# PA_Channel.net
KiCad netlist of a schematic drawn in Altium Designer
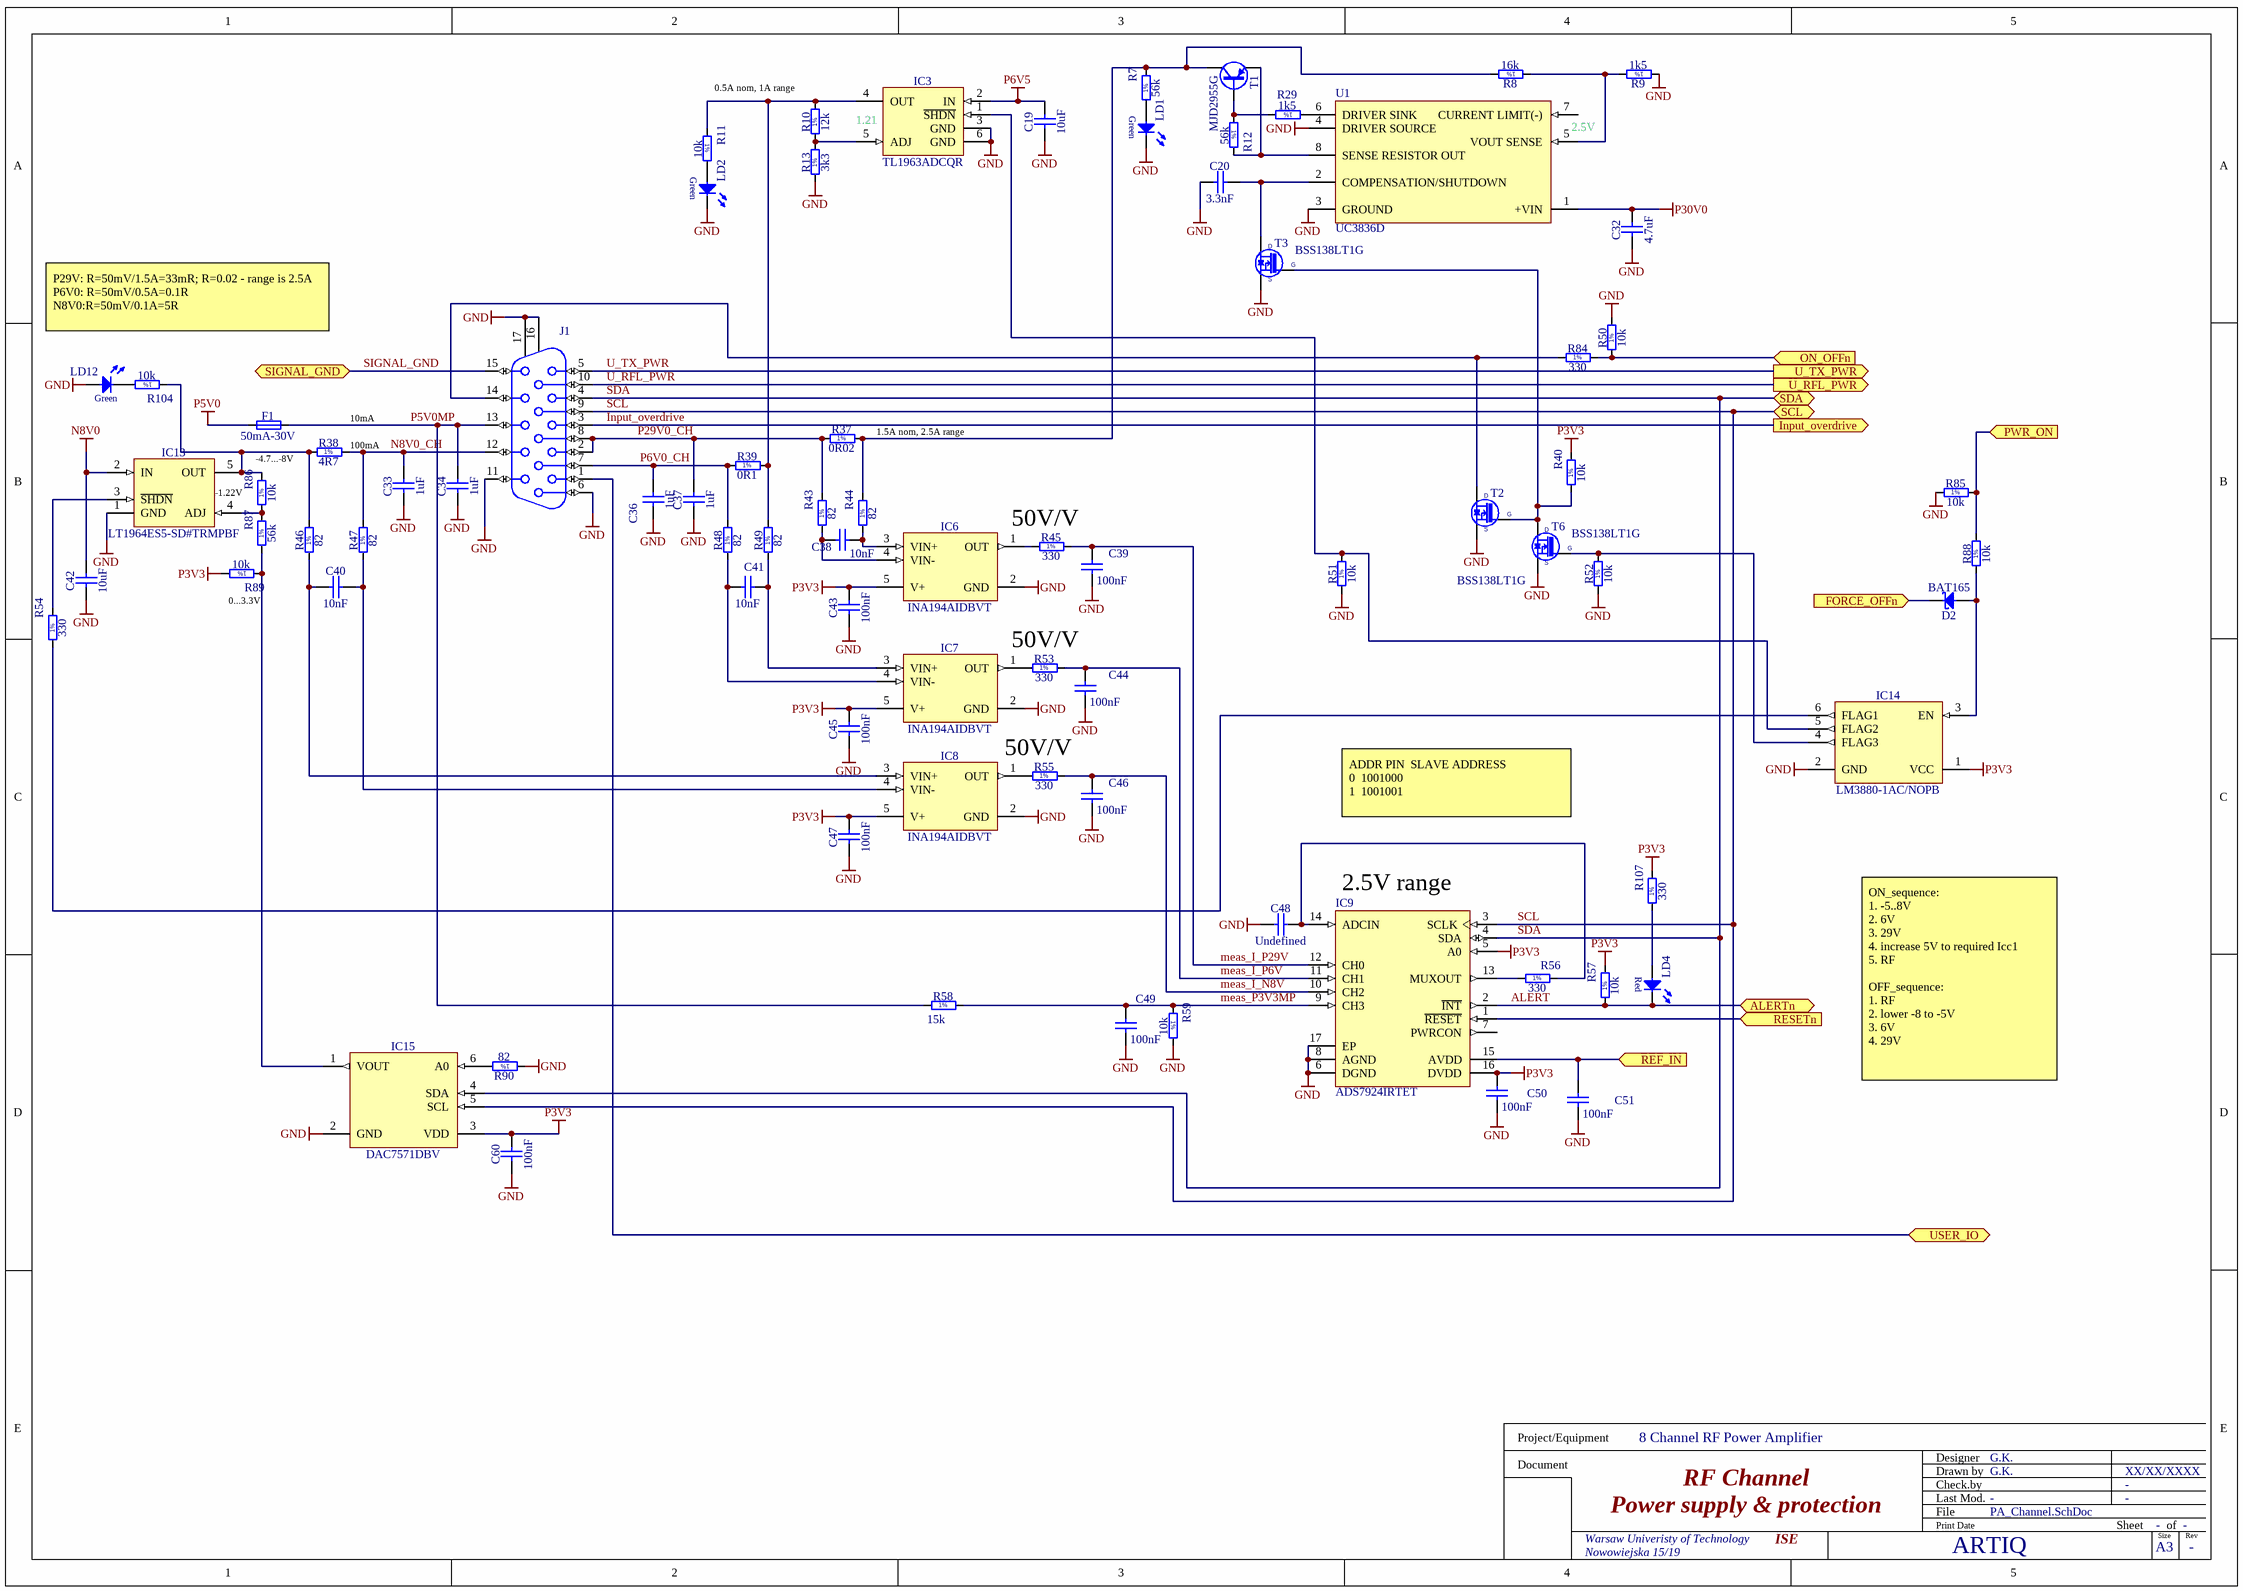
[diagram p0: PA_Channel.SchDoc]

(export (version "E")
  (design (tool "Eeschema 10.0.6"))
  (components
    (comp (ref "C19")
      (value "10uF")
      (footprint "CAPC3216X140N")
      (description "Non-polarised capacitor")
      (fields
        (field (name "PART NUMBER") "CC1206_10UF_16V_10%_X7R")
        (field (name "VOLTAGE") "16V")
        (field (name "AUTHOR") "CERN DEM JLC")
      )
      (libsource (lib "Capacitors") (part "Capacitor - non polarized"))
    )
    (comp (ref "C20")
      (value "3.3nF")
      (footprint "CAPC1005X55N")
      (description "Non-polarised capacitor")
      (fields
        (field (name "PART NUMBER") "CC0402_3.3NF_50V_10%_X7R")
        (field (name "VOLTAGE") "50V")
        (field (name "AUTHOR") "CERN DEM JLC")
      )
      (libsource (lib "Capacitors") (part "Capacitor - non polarized"))
    )
    (comp (ref "C32")
      (value "4.7uF")
      (footprint "CAPC3216X180N")
      (description "Non-polarised capacitor")
      (fields
        (field (name "PART NUMBER") "CC1206_4.7UF_50V_+80%-20%_Y5V")
        (field (name "VOLTAGE") "50V")
        (field (name "AUTHOR") "CERN DEM JLC")
      )
      (libsource (lib "Capacitors") (part "Capacitor - non polarized"))
    )
    (comp (ref "C33")
      (value "1uF")
      (footprint "CAPC2012X110N")
      (description "Non-polarised capacitor")
      (fields
        (field (name "PART NUMBER") "CC0805_1UF_50V_10%_X7R")
        (field (name "VOLTAGE") "50V")
        (field (name "AUTHOR") "CERN DEM JLC")
      )
      (libsource (lib "Capacitors") (part "Capacitor - non polarized"))
    )
    (comp (ref "C34")
      (value "1uF")
      (footprint "CAPC2012X110N")
      (description "Non-polarised capacitor")
      (fields
        (field (name "PART NUMBER") "CC0805_1UF_50V_10%_X7R")
        (field (name "VOLTAGE") "50V")
        (field (name "AUTHOR") "CERN DEM JLC")
      )
      (libsource (lib "Capacitors") (part "Capacitor - non polarized"))
    )
    (comp (ref "C36")
      (value "1uF")
      (footprint "CAPC2012X110N")
      (description "Non-polarised capacitor")
      (fields
        (field (name "PART NUMBER") "CC0805_1UF_50V_10%_X7R")
        (field (name "VOLTAGE") "50V")
        (field (name "AUTHOR") "CERN DEM JLC")
      )
      (libsource (lib "Capacitors") (part "Capacitor - non polarized"))
    )
    (comp (ref "C37")
      (value "1uF")
      (footprint "CAPC2012X110N")
      (description "Non-polarised capacitor")
      (fields
        (field (name "PART NUMBER") "CC0805_1UF_50V_10%_X7R")
        (field (name "VOLTAGE") "50V")
        (field (name "AUTHOR") "CERN DEM JLC")
      )
      (libsource (lib "Capacitors") (part "Capacitor - non polarized"))
    )
    (comp (ref "C38")
      (value "10nF")
      (footprint "CAPC1608X87N")
      (description "Non-polarised capacitor")
      (fields
        (field (name "PART NUMBER") "CC0603_10NF_50V_5%_C0G")
        (field (name "VOLTAGE") "50V")
        (field (name "AUTHOR") "CERN DEM JLC")
      )
      (libsource (lib "Capacitors") (part "Capacitor - non polarized"))
    )
    (comp (ref "C39")
      (value "100nF")
      (footprint "CAPC1005X55N")
      (description "Non-polarised capacitor")
      (fields
        (field (name "PART NUMBER") "CC0402_100NF_16V_10%_X7R")
        (field (name "VOLTAGE") "16V")
        (field (name "AUTHOR") "CERN DEM JLC")
      )
      (libsource (lib "Capacitors") (part "Capacitor - non polarized"))
    )
    (comp (ref "C40")
      (value "10nF")
      (footprint "CAPC1608X87N")
      (description "Non-polarised capacitor")
      (fields
        (field (name "PART NUMBER") "CC0603_10NF_50V_5%_C0G")
        (field (name "VOLTAGE") "50V")
        (field (name "AUTHOR") "CERN DEM JLC")
      )
      (libsource (lib "Capacitors") (part "Capacitor - non polarized"))
    )
    (comp (ref "C41")
      (value "10nF")
      (footprint "CAPC1608X87N")
      (description "Non-polarised capacitor")
      (fields
        (field (name "PART NUMBER") "CC0603_10NF_50V_5%_C0G")
        (field (name "VOLTAGE") "50V")
        (field (name "AUTHOR") "CERN DEM JLC")
      )
      (libsource (lib "Capacitors") (part "Capacitor - non polarized"))
    )
    (comp (ref "C42")
      (value "10uF")
      (footprint "CAPC3216X140N")
      (description "Non-polarised capacitor")
      (fields
        (field (name "PART NUMBER") "CC1206_10UF_16V_10%_X7R")
        (field (name "VOLTAGE") "16V")
        (field (name "AUTHOR") "CERN DEM JLC")
      )
      (libsource (lib "Capacitors") (part "Capacitor - non polarized"))
    )
    (comp (ref "C43")
      (value "100nF")
      (footprint "CAPC1005X55N")
      (description "Non-polarised capacitor")
      (fields
        (field (name "PART NUMBER") "CC0402_100NF_16V_10%_X7R")
        (field (name "VOLTAGE") "16V")
        (field (name "AUTHOR") "CERN DEM JLC")
      )
      (libsource (lib "Capacitors") (part "Capacitor - non polarized"))
    )
    (comp (ref "C44")
      (value "100nF")
      (footprint "CAPC1005X55N")
      (description "Non-polarised capacitor")
      (fields
        (field (name "PART NUMBER") "CC0402_100NF_16V_10%_X7R")
        (field (name "VOLTAGE") "16V")
        (field (name "AUTHOR") "CERN DEM JLC")
      )
      (libsource (lib "Capacitors") (part "Capacitor - non polarized"))
    )
    (comp (ref "C45")
      (value "100nF")
      (footprint "CAPC1005X55N")
      (description "Non-polarised capacitor")
      (fields
        (field (name "PART NUMBER") "CC0402_100NF_16V_10%_X7R")
        (field (name "VOLTAGE") "16V")
        (field (name "AUTHOR") "CERN DEM JLC")
      )
      (libsource (lib "Capacitors") (part "Capacitor - non polarized"))
    )
    (comp (ref "C46")
      (value "100nF")
      (footprint "CAPC1005X55N")
      (description "Non-polarised capacitor")
      (fields
        (field (name "PART NUMBER") "CC0402_100NF_16V_10%_X7R")
        (field (name "VOLTAGE") "16V")
        (field (name "AUTHOR") "CERN DEM JLC")
      )
      (libsource (lib "Capacitors") (part "Capacitor - non polarized"))
    )
    (comp (ref "C47")
      (value "100nF")
      (footprint "CAPC1005X55N")
      (description "Non-polarised capacitor")
      (fields
        (field (name "PART NUMBER") "CC0402_100NF_16V_10%_X7R")
        (field (name "VOLTAGE") "16V")
        (field (name "AUTHOR") "CERN DEM JLC")
      )
      (libsource (lib "Capacitors") (part "Capacitor - non polarized"))
    )
    (comp (ref "C48")
      (value "Undefined")
      (footprint "CAPC1005X55N")
      (description "Non-polarised capacitor")
      (fields (field (name "PART NUMBER") "CC0402_NO-VALUE") (field (name "AUTHOR") "CERN DEM JLC"))
      (libsource (lib "Capacitors") (part "Capacitor - non polarized"))
    )
    (comp (ref "C49")
      (value "100nF")
      (footprint "CAPC1005X55N")
      (description "Non-polarised capacitor")
      (fields
        (field (name "PART NUMBER") "CC0402_100NF_16V_10%_X7R")
        (field (name "VOLTAGE") "16V")
        (field (name "AUTHOR") "CERN DEM JLC")
      )
      (libsource (lib "Capacitors") (part "Capacitor - non polarized"))
    )
    (comp (ref "C50")
      (value "100nF")
      (footprint "CAPC1005X55N")
      (description "Non-polarised capacitor")
      (fields
        (field (name "PART NUMBER") "CC0402_100NF_16V_10%_X7R")
        (field (name "VOLTAGE") "16V")
        (field (name "AUTHOR") "CERN DEM JLC")
      )
      (libsource (lib "Capacitors") (part "Capacitor - non polarized"))
    )
    (comp (ref "C51")
      (value "100nF")
      (footprint "CAPC1005X55N")
      (description "Non-polarised capacitor")
      (fields
        (field (name "PART NUMBER") "CC0402_100NF_16V_10%_X7R")
        (field (name "VOLTAGE") "16V")
        (field (name "AUTHOR") "CERN DEM JLC")
      )
      (libsource (lib "Capacitors") (part "Capacitor - non polarized"))
    )
    (comp (ref "C60")
      (value "100nF")
      (footprint "CAPC1005X55N")
      (description "Non-polarised capacitor")
      (fields
        (field (name "PART NUMBER") "CC0402_100NF_16V_10%_X7R")
        (field (name "VOLTAGE") "16V")
        (field (name "AUTHOR") "CERN DEM JLC")
      )
      (libsource (lib "Capacitors") (part "Capacitor - non polarized"))
    )
    (comp (ref "D2")
      (value "BAT165")
      (footprint "SOD2512X110N")
      (description "Schottky Diode")
      (fields
        (field (name "VOLTAGE") "40V")
        (field (name "POWER") "750mA")
        (field (name "AUTHOR") "CERN DEM JLC")
      )
      (libsource (lib "ICs And Semiconductors") (part "Diode Schottky"))
    )
    (comp (ref "F1")
      (value "50mA-30V")
      (footprint "FUSRC3226X85N")
      (description "Fuse")
      (fields
        (field (name "PART NUMBER") "FUSR1210_TYCO-MICROSMD005F")
        (field (name "MANUFACTURER") "TYCO ELECTRONICS")
        (field (name "AUTHOR") "CERN DEM JLC")
      )
      (libsource (lib "Eletro-mechanical") (part "Fuse"))
    )
    (comp (ref "IC3")
      (value "TL1963ADCQR")
      (footprint "SOT127P700X180-6N")
      (description "1.2V to 20V, 1.5A, Fast Transient Response, Low Noise, LDO Adjustable Regulator")
      (fields (field (name "MANUFACTURER") "TEXAS INSTRUMENTS") (field (name "AUTHOR") "CERN DEM JLC"))
      (libsource (lib "ICs And Semiconductors") (part "TL1963ADCQR"))
    )
    (comp (ref "IC6")
      (value "INA194AIDBVT")
      (footprint "SOT95P280X145-5N")
      (description "Current Shunt Monitor -16V to +80V Common-Mode Range")
      (fields (field (name "MANUFACTURER") "TEXAS INSTRUMENTS") (field (name "AUTHOR") "CERN DEM JLC"))
      (libsource (lib "ICs And Semiconductors") (part "INA194"))
    )
    (comp (ref "IC7")
      (value "INA194AIDBVT")
      (footprint "SOT95P280X145-5N")
      (description "Current Shunt Monitor -16V to +80V Common-Mode Range")
      (fields (field (name "MANUFACTURER") "TEXAS INSTRUMENTS") (field (name "AUTHOR") "CERN DEM JLC"))
      (libsource (lib "ICs And Semiconductors") (part "INA194"))
    )
    (comp (ref "IC8")
      (value "INA194AIDBVT")
      (footprint "SOT95P280X145-5N")
      (description "Current Shunt Monitor -16V to +80V Common-Mode Range")
      (fields (field (name "MANUFACTURER") "TEXAS INSTRUMENTS") (field (name "AUTHOR") "CERN DEM JLC"))
      (libsource (lib "ICs And Semiconductors") (part "INA194"))
    )
    (comp (ref "IC9")
      (value "ADS7924IRTET")
      (footprint "TI-RTE16-1700X1700TP_V")
      (fields (field (name "MANUFACTURER") "Texas Instruments"))
      (libsource (lib "Altium Content Vault") (part "CMP-0003-02162-1"))
    )
    (comp (ref "IC13")
      (value "LT1964ES5-SD#TRMPBF")
      (footprint "SOT95P280X100-5N")
      (description "200mA, Low Noise, Low Dropout Negative Micropower Regulator")
      (fields (field (name "MANUFACTURER") "LINEAR TECHNOLOGY") (field (name "AUTHOR") "CERN DEM JLC"))
      (libsource (lib "ICs And Semiconductors") (part "LT1964-SD"))
    )
    (comp (ref "IC14")
      (value "LM3880-1AC/NOPB")
      (footprint "SOT95P280X145-6N")
      (description "Simple Power Sequencer")
      (fields (field (name "MANUFACTURER") "TEXAS INSTRUMENTS") (field (name "AUTHOR") "CERN DEM MR"))
      (libsource (lib "ICs And Semiconductors") (part "LM3880"))
    )
    (comp (ref "IC15")
      (value "DAC7571DBV")
      (footprint "SOT95P280X145-6N")
      (description "+2.7 V to +5.5 V, I2C Interface (Receive Only), Voltage Output, 12-Bit Digital-To-Analog Converter")
      (fields (field (name "MANUFACTURER") "TEXAS INSTRUMENTS") (field (name "AUTHOR") "CERN DEM MR"))
      (libsource (lib "ICs And Semiconductors") (part "DAC7571"))
    )
    (comp (ref "J1")
      (value "HD-Sub")
      (footprint "TYCO_1932144-1")
      (description "Connector High Density D-sub 15 Female")
      (fields
        (field (name "PART NUMBER") "TYCO_1932144-1")
        (field (name "MANUFACTURER") "TYCO ELECTRONICS")
        (field (name "AUTHOR") "GK")
      )
      (libsource (lib "LIBRARY_SCH") (part "CON_DB15_V_F_1932144-1"))
    )
    (comp (ref "LD1")
      (value "Green")
      (footprint "LED_KINGBRIGHT_KPH-1608CGCK")
      (description "LED Green 1C 2A")
      (fields
        (field (name "PART NUMBER") "LED_KINGBRIGHT_KPH-1608CGCK")
        (field (name "MANUFACTURER") "KINGBRIGHT")
        (field (name "AUTHOR") "CERN DEM JLC")
      )
      (libsource (lib "ICs And Semiconductors") (part "LED Green 1C 2A"))
    )
    (comp (ref "LD2")
      (value "Green")
      (footprint "LED_KINGBRIGHT_KPH-1608CGCK")
      (description "LED Green 1C 2A")
      (fields
        (field (name "PART NUMBER") "LED_KINGBRIGHT_KPH-1608CGCK")
        (field (name "MANUFACTURER") "KINGBRIGHT")
        (field (name "AUTHOR") "CERN DEM JLC")
      )
      (libsource (lib "ICs And Semiconductors") (part "LED Green 1C 2A"))
    )
    (comp (ref "LD4")
      (value "Hyper Red")
      (footprint "LED_KINGBRIGHT_KPH-1608SURCK")
      (description "LED Red 1C 2A")
      (fields
        (field (name "PART NUMBER") "LED_KINGBRIGHT_KPH-1608SURCK")
        (field (name "MANUFACTURER") "KINGBRIGHT")
        (field (name "AUTHOR") "CERN DEM JLC")
      )
      (libsource (lib "ICs And Semiconductors") (part "LED Red 1C 2A"))
    )
    (comp (ref "LD12")
      (value "Green")
      (footprint "LED_KINGBRIGHT_KPH-1608CGCK")
      (description "LED Green 1C 2A")
      (fields
        (field (name "PART NUMBER") "LED_KINGBRIGHT_KPH-1608CGCK")
        (field (name "MANUFACTURER") "KINGBRIGHT")
        (field (name "AUTHOR") "CERN DEM JLC")
      )
      (libsource (lib "ICs And Semiconductors") (part "LED Green 1C 2A"))
    )
    (comp (ref "R7")
      (value "56k")
      (footprint "RESC1608X55N")
      (description "Resistor - 1%")
      (fields
        (field (name "PART NUMBER") "R0603_56K_1%_0.1W_100PPM")
        (field (name "POWER") "0.1W")
        (field (name "AUTHOR") "CERN DEM JLC")
      )
      (libsource (lib "Resistors") (part "Resistor - 1%"))
    )
    (comp (ref "R8")
      (value "16k")
      (footprint "RESC1608X55N")
      (description "Resistor - 1%")
      (fields
        (field (name "PART NUMBER") "R0603_16K_1%_0.1W_100PPM")
        (field (name "POWER") "0.1W")
        (field (name "AUTHOR") "CERN DEM JLC")
      )
      (libsource (lib "Resistors") (part "Resistor - 1%"))
    )
    (comp (ref "R9")
      (value "1k5")
      (footprint "RESC1608X55N")
      (description "Resistor - 1%")
      (fields
        (field (name "PART NUMBER") "R0603_1K5_1%_0.1W_100PPM")
        (field (name "POWER") "0.1W")
        (field (name "AUTHOR") "CERN DEM JLC")
      )
      (libsource (lib "Resistors") (part "Resistor - 1%"))
    )
    (comp (ref "R10")
      (value "12k")
      (footprint "RESC1005X40N")
      (description "Resistor - 1%")
      (fields
        (field (name "PART NUMBER") "R0402_12K_1%_0.0625W_100PPM")
        (field (name "POWER") "0.0625W")
        (field (name "AUTHOR") "CERN DEM JLC")
      )
      (libsource (lib "Resistors") (part "Resistor - 1%"))
    )
    (comp (ref "R11")
      (value "10k")
      (footprint "RESC1005X40N")
      (description "Resistor - 1%")
      (fields
        (field (name "PART NUMBER") "R0402_10K_1%_0.0625W_100PPM")
        (field (name "POWER") "0.0625W")
        (field (name "AUTHOR") "CERN DEM JLC")
      )
      (libsource (lib "Resistors") (part "Resistor - 1%"))
    )
    (comp (ref "R12")
      (value "56k")
      (footprint "RESC1608X55N")
      (description "Resistor - 1%")
      (fields
        (field (name "PART NUMBER") "R0603_56K_1%_0.1W_100PPM")
        (field (name "POWER") "0.1W")
        (field (name "AUTHOR") "CERN DEM JLC")
      )
      (libsource (lib "Resistors") (part "Resistor - 1%"))
    )
    (comp (ref "R13")
      (value "3k3")
      (footprint "RESC1005X40N")
      (description "Resistor - 1%")
      (fields
        (field (name "PART NUMBER") "R0402_3K3_1%_0.0625W_100PPM")
        (field (name "POWER") "0.0625W")
        (field (name "AUTHOR") "CERN DEM JLC")
      )
      (libsource (lib "Resistors") (part "Resistor - 1%"))
    )
    (comp (ref "R29")
      (value "1k5")
      (footprint "RESC1608X55N")
      (description "Resistor - 1%")
      (fields
        (field (name "PART NUMBER") "R0603_1K5_1%_0.1W_100PPM")
        (field (name "POWER") "0.1W")
        (field (name "AUTHOR") "CERN DEM JLC")
      )
      (libsource (lib "Resistors") (part "Resistor - 1%"))
    )
    (comp (ref "R37")
      (value "0R02")
      (footprint "RESC3216X80N")
      (description "Resistor - 1%")
      (fields
        (field (name "PART NUMBER") "R1206_0R02_1%_1W_150PPM")
        (field (name "POWER") "1W")
        (field (name "AUTHOR") "CERN DEM JLC")
      )
      (libsource (lib "Resistors") (part "Resistor - 1%"))
    )
    (comp (ref "R38")
      (value "4R7")
      (footprint "RESC3216X65N")
      (description "Resistor - 1%")
      (fields
        (field (name "PART NUMBER") "R1206_4R7_1%_0.25W_200PPM")
        (field (name "POWER") "0.25W")
        (field (name "AUTHOR") "CERN DEM JLC")
      )
      (libsource (lib "Resistors") (part "Resistor - 1%"))
    )
    (comp (ref "R39")
      (value "0R1")
      (footprint "RESC3216X65N")
      (description "Resistor - 1%")
      (fields
        (field (name "PART NUMBER") "R1206_0R1_1%_0.25W_100PPM_YAGEO_PT")
        (field (name "POWER") "0.25W")
        (field (name "AUTHOR") "CERN DEM JMW")
      )
      (libsource (lib "Resistors") (part "Resistor - 1%"))
    )
    (comp (ref "R40")
      (value "10k")
      (footprint "RESC1005X40N")
      (description "Resistor - 1%")
      (fields
        (field (name "PART NUMBER") "R0402_10K_1%_0.0625W_100PPM")
        (field (name "POWER") "0.0625W")
        (field (name "AUTHOR") "CERN DEM JLC")
      )
      (libsource (lib "Resistors") (part "Resistor - 1%"))
    )
    (comp (ref "R43")
      (value "82")
      (footprint "RESC1005X40N")
      (description "Resistor - 1%")
      (fields
        (field (name "PART NUMBER") "R0402_82R_1%_0.0625W_100PPM")
        (field (name "POWER") "0.0625W")
        (field (name "AUTHOR") "CERN DEM JLC")
      )
      (libsource (lib "Resistors") (part "Resistor - 1%"))
    )
    (comp (ref "R44")
      (value "82")
      (footprint "RESC1005X40N")
      (description "Resistor - 1%")
      (fields
        (field (name "PART NUMBER") "R0402_82R_1%_0.0625W_100PPM")
        (field (name "POWER") "0.0625W")
        (field (name "AUTHOR") "CERN DEM JLC")
      )
      (libsource (lib "Resistors") (part "Resistor - 1%"))
    )
    (comp (ref "R45")
      (value "330")
      (footprint "RESC1608X55N")
      (description "Resistor - 1%")
      (fields
        (field (name "PART NUMBER") "R0603_330R_1%_0.1W_100PPM")
        (field (name "POWER") "0.1W")
        (field (name "AUTHOR") "CERN DEM JLC")
      )
      (libsource (lib "Resistors") (part "Resistor - 1%"))
    )
    (comp (ref "R46")
      (value "82")
      (footprint "RESC1005X40N")
      (description "Resistor - 1%")
      (fields
        (field (name "PART NUMBER") "R0402_82R_1%_0.0625W_100PPM")
        (field (name "POWER") "0.0625W")
        (field (name "AUTHOR") "CERN DEM JLC")
      )
      (libsource (lib "Resistors") (part "Resistor - 1%"))
    )
    (comp (ref "R47")
      (value "82")
      (footprint "RESC1005X40N")
      (description "Resistor - 1%")
      (fields
        (field (name "PART NUMBER") "R0402_82R_1%_0.0625W_100PPM")
        (field (name "POWER") "0.0625W")
        (field (name "AUTHOR") "CERN DEM JLC")
      )
      (libsource (lib "Resistors") (part "Resistor - 1%"))
    )
    (comp (ref "R48")
      (value "82")
      (footprint "RESC1005X40N")
      (description "Resistor - 1%")
      (fields
        (field (name "PART NUMBER") "R0402_82R_1%_0.0625W_100PPM")
        (field (name "POWER") "0.0625W")
        (field (name "AUTHOR") "CERN DEM JLC")
      )
      (libsource (lib "Resistors") (part "Resistor - 1%"))
    )
    (comp (ref "R49")
      (value "82")
      (footprint "RESC1005X40N")
      (description "Resistor - 1%")
      (fields
        (field (name "PART NUMBER") "R0402_82R_1%_0.0625W_100PPM")
        (field (name "POWER") "0.0625W")
        (field (name "AUTHOR") "CERN DEM JLC")
      )
      (libsource (lib "Resistors") (part "Resistor - 1%"))
    )
    (comp (ref "R50")
      (value "10k")
      (footprint "RESC1005X40N")
      (description "Resistor - 1%")
      (fields
        (field (name "PART NUMBER") "R0402_10K_1%_0.0625W_100PPM")
        (field (name "POWER") "0.0625W")
        (field (name "AUTHOR") "CERN DEM JLC")
      )
      (libsource (lib "Resistors") (part "Resistor - 1%"))
    )
    (comp (ref "R51")
      (value "10k")
      (footprint "RESC1005X40N")
      (description "Resistor - 1%")
      (fields
        (field (name "PART NUMBER") "R0402_10K_1%_0.0625W_100PPM")
        (field (name "POWER") "0.0625W")
        (field (name "AUTHOR") "CERN DEM JLC")
      )
      (libsource (lib "Resistors") (part "Resistor - 1%"))
    )
    (comp (ref "R52")
      (value "10k")
      (footprint "RESC1005X40N")
      (description "Resistor - 1%")
      (fields
        (field (name "PART NUMBER") "R0402_10K_1%_0.0625W_100PPM")
        (field (name "POWER") "0.0625W")
        (field (name "AUTHOR") "CERN DEM JLC")
      )
      (libsource (lib "Resistors") (part "Resistor - 1%"))
    )
    (comp (ref "R53")
      (value "330")
      (footprint "RESC1608X55N")
      (description "Resistor - 1%")
      (fields
        (field (name "PART NUMBER") "R0603_330R_1%_0.1W_100PPM")
        (field (name "POWER") "0.1W")
        (field (name "AUTHOR") "CERN DEM JLC")
      )
      (libsource (lib "Resistors") (part "Resistor - 1%"))
    )
    (comp (ref "R54")
      (value "330")
      (footprint "RESC1608X55N")
      (description "Resistor - 1%")
      (fields
        (field (name "PART NUMBER") "R0603_330R_1%_0.1W_100PPM")
        (field (name "POWER") "0.1W")
        (field (name "AUTHOR") "CERN DEM JLC")
      )
      (libsource (lib "Resistors") (part "Resistor - 1%"))
    )
    (comp (ref "R55")
      (value "330")
      (footprint "RESC1608X55N")
      (description "Resistor - 1%")
      (fields
        (field (name "PART NUMBER") "R0603_330R_1%_0.1W_100PPM")
        (field (name "POWER") "0.1W")
        (field (name "AUTHOR") "CERN DEM JLC")
      )
      (libsource (lib "Resistors") (part "Resistor - 1%"))
    )
    (comp (ref "R56")
      (value "330")
      (footprint "RESC1608X55N")
      (description "Resistor - 1%")
      (fields
        (field (name "PART NUMBER") "R0603_330R_1%_0.1W_100PPM")
        (field (name "POWER") "0.1W")
        (field (name "AUTHOR") "CERN DEM JLC")
      )
      (libsource (lib "Resistors") (part "Resistor - 1%"))
    )
    (comp (ref "R57")
      (value "10k")
      (footprint "RESC1005X40N")
      (description "Resistor - 1%")
      (fields
        (field (name "PART NUMBER") "R0402_10K_1%_0.0625W_100PPM")
        (field (name "POWER") "0.0625W")
        (field (name "AUTHOR") "CERN DEM JLC")
      )
      (libsource (lib "Resistors") (part "Resistor - 1%"))
    )
    (comp (ref "R58")
      (value "15k")
      (footprint "RESC1005X40N")
      (description "Resistor - 1%")
      (fields
        (field (name "PART NUMBER") "R0402_15K_1%_0.0625W_100PPM")
        (field (name "POWER") "0.0625W")
        (field (name "AUTHOR") "CERN DEM JMW")
      )
      (libsource (lib "Resistors") (part "Resistor - 1%"))
    )
    (comp (ref "R59")
      (value "10k")
      (footprint "RESC1005X40N")
      (description "Resistor - 1%")
      (fields
        (field (name "PART NUMBER") "R0402_10K_1%_0.0625W_100PPM")
        (field (name "POWER") "0.0625W")
        (field (name "AUTHOR") "CERN DEM JLC")
      )
      (libsource (lib "Resistors") (part "Resistor - 1%"))
    )
    (comp (ref "R84")
      (value "330")
      (footprint "RESC1608X55N")
      (description "Resistor - 1%")
      (fields
        (field (name "PART NUMBER") "R0603_330R_1%_0.1W_100PPM")
        (field (name "POWER") "0.1W")
        (field (name "AUTHOR") "CERN DEM JLC")
      )
      (libsource (lib "Resistors") (part "Resistor - 1%"))
    )
    (comp (ref "R85")
      (value "10k")
      (footprint "RESC1005X40N")
      (description "Resistor - 1%")
      (fields
        (field (name "PART NUMBER") "R0402_10K_1%_0.0625W_100PPM")
        (field (name "POWER") "0.0625W")
        (field (name "AUTHOR") "CERN DEM JLC")
      )
      (libsource (lib "Resistors") (part "Resistor - 1%"))
    )
    (comp (ref "R86")
      (value "10k")
      (footprint "RESC1005X40N")
      (description "Resistor - 1%")
      (fields
        (field (name "PART NUMBER") "R0402_10K_1%_0.0625W_100PPM")
        (field (name "POWER") "0.0625W")
        (field (name "AUTHOR") "CERN DEM JLC")
      )
      (libsource (lib "Resistors") (part "Resistor - 1%"))
    )
    (comp (ref "R87")
      (value "56k")
      (footprint "RESC1608X55N")
      (description "Resistor - 1%")
      (fields
        (field (name "PART NUMBER") "R0603_56K_1%_0.1W_100PPM")
        (field (name "POWER") "0.1W")
        (field (name "AUTHOR") "CERN DEM JLC")
      )
      (libsource (lib "Resistors") (part "Resistor - 1%"))
    )
    (comp (ref "R88")
      (value "10k")
      (footprint "RESC1005X40N")
      (description "Resistor - 1%")
      (fields
        (field (name "PART NUMBER") "R0402_10K_1%_0.0625W_100PPM")
        (field (name "POWER") "0.0625W")
        (field (name "AUTHOR") "CERN DEM JLC")
      )
      (libsource (lib "Resistors") (part "Resistor - 1%"))
    )
    (comp (ref "R89")
      (value "10k")
      (footprint "RESC1005X40N")
      (description "Resistor - 1%")
      (fields
        (field (name "PART NUMBER") "R0402_10K_1%_0.0625W_100PPM")
        (field (name "POWER") "0.0625W")
        (field (name "AUTHOR") "CERN DEM JLC")
      )
      (libsource (lib "Resistors") (part "Resistor - 1%"))
    )
    (comp (ref "R90")
      (value "82")
      (footprint "RESC1005X40N")
      (description "Resistor - 1%")
      (fields
        (field (name "PART NUMBER") "R0402_82R_1%_0.0625W_100PPM")
        (field (name "POWER") "0.0625W")
        (field (name "AUTHOR") "CERN DEM JLC")
      )
      (libsource (lib "Resistors") (part "Resistor - 1%"))
    )
    (comp (ref "R104")
      (value "10k")
      (footprint "RESC1005X40N")
      (description "Resistor - 1%")
      (fields
        (field (name "PART NUMBER") "R0402_10K_1%_0.0625W_100PPM")
        (field (name "POWER") "0.0625W")
        (field (name "AUTHOR") "CERN DEM JLC")
      )
      (libsource (lib "Resistors") (part "Resistor - 1%"))
    )
    (comp (ref "R107")
      (value "330")
      (footprint "RESC1608X55N")
      (description "Resistor - 1%")
      (fields
        (field (name "PART NUMBER") "R0603_330R_1%_0.1W_100PPM")
        (field (name "POWER") "0.1W")
        (field (name "AUTHOR") "CERN DEM JLC")
      )
      (libsource (lib "Resistors") (part "Resistor - 1%"))
    )
    (comp (ref "T1")
      (value "MJD2955G")
      (footprint "TO228P991X239-3N-R552X520")
      (description "PNP Transistor")
      (fields (field (name "MANUFACTURER") "ON SEMICONDUCTOR") (field (name "AUTHOR") "CERN DEM JLC"))
      (libsource (lib "ICs And Semiconductors") (part "PNP B1 E2 C3"))
    )
    (comp (ref "T2")
      (value "BSS138LT1G")
      (footprint "SOT95P240X110-3N")
      (description "N-CHANNEL MOSFET WITH DIODE")
      (fields (field (name "MANUFACTURER") "ON SEMICONDUCTOR") (field (name "AUTHOR") "CERN DEM JLC"))
      (libsource (lib "ICs And Semiconductors") (part "N-MOSFET-D 1G 2S 3D"))
    )
    (comp (ref "T3")
      (value "BSS138LT1G")
      (footprint "SOT95P240X110-3N")
      (description "N-CHANNEL MOSFET WITH DIODE")
      (fields (field (name "MANUFACTURER") "ON SEMICONDUCTOR") (field (name "AUTHOR") "CERN DEM JLC"))
      (libsource (lib "ICs And Semiconductors") (part "N-MOSFET-D 1G 2S 3D"))
    )
    (comp (ref "T6")
      (value "BSS138LT1G")
      (footprint "SOT95P240X110-3N")
      (description "N-CHANNEL MOSFET WITH DIODE")
      (fields (field (name "MANUFACTURER") "ON SEMICONDUCTOR") (field (name "AUTHOR") "CERN DEM JLC"))
      (libsource (lib "ICs And Semiconductors") (part "N-MOSFET-D 1G 2S 3D"))
    )
    (comp (ref "U1")
      (value "UC3836D")
      (footprint "D0008A_M")
      (fields (field (name "MANUFACTURER") "Texas Instruments"))
      (libsource (lib "Altium Content Vault") (part "CMP-0322-00047-2"))
    )
  )
  (nets
    (net (code "1") (name "/ALERT") (class "Default")
      (node (ref "IC9") (pin "2") (pinfunction "~{INT}_2") (pintype "output"))
      (node (ref "LD4") (pin "1") (pinfunction "C_1") (pintype "passive"))
      (node (ref "R57") (pin "1") (pinfunction "1_1") (pintype "passive"))
    )
    (net (code "2") (name "/FORCE_OFFn") (class "Default")
      (node (ref "D2") (pin "1") (pinfunction "C_1") (pintype "passive"))
    )
    (net (code "3") (name "/Input_overdrive") (class "Default")
      (node (ref "J1") (pin "3") (pinfunction "3_3") (pintype "bidirectional"))
    )
    (net (code "4") (name "/N8V0_CH") (class "Default")
      (node (ref "C33") (pin "2") (pinfunction "2_2") (pintype "passive"))
      (node (ref "J1") (pin "12") (pinfunction "12_12") (pintype "bidirectional"))
      (node (ref "R38") (pin "2") (pinfunction "2_2") (pintype "passive"))
      (node (ref "R47") (pin "2") (pinfunction "2_2") (pintype "passive"))
    )
    (net (code "5") (name "/ON_OFFn") (class "Default")
      (node (ref "R50") (pin "1") (pinfunction "1_1") (pintype "passive"))
      (node (ref "R84") (pin "2") (pinfunction "2_2") (pintype "passive"))
    )
    (net (code "6") (name "/P5V0MP") (class "Default")
      (node (ref "C34") (pin "2") (pinfunction "2_2") (pintype "passive"))
      (node (ref "F1") (pin "2") (pinfunction "2_2") (pintype "passive"))
      (node (ref "J1") (pin "13") (pinfunction "13_13") (pintype "bidirectional"))
      (node (ref "R58") (pin "1") (pinfunction "1_1") (pintype "passive"))
    )
    (net (code "7") (name "/P6V0_CH") (class "Default")
      (node (ref "C36") (pin "2") (pinfunction "2_2") (pintype "passive"))
      (node (ref "J1") (pin "7") (pinfunction "7_7") (pintype "bidirectional"))
      (node (ref "R39") (pin "1") (pinfunction "1_1") (pintype "passive"))
      (node (ref "R48") (pin "2") (pinfunction "2_2") (pintype "passive"))
    )
    (net (code "8") (name "/P29V0_CH") (class "Default")
      (node (ref "C37") (pin "2") (pinfunction "2_2") (pintype "passive"))
      (node (ref "J1") (pin "2") (pinfunction "2_2") (pintype "bidirectional"))
      (node (ref "J1") (pin "8") (pinfunction "8_8") (pintype "bidirectional"))
      (node (ref "R37") (pin "1") (pinfunction "1_1") (pintype "passive"))
      (node (ref "R43") (pin "2") (pinfunction "2_2") (pintype "passive"))
    )
    (net (code "9") (name "/PWR_ON") (class "Default")
      (node (ref "R85") (pin "2") (pinfunction "2_2") (pintype "passive"))
      (node (ref "R88") (pin "2") (pinfunction "2_2") (pintype "passive"))
    )
    (net (code "10") (name "/REF_IN") (class "Default")
      (node (ref "C51") (pin "1") (pinfunction "1_1") (pintype "passive"))
      (node (ref "IC9") (pin "15") (pinfunction "AVDD_15") (pintype "power_in"))
    )
    (net (code "11") (name "/RESETn") (class "Default")
      (node (ref "IC9") (pin "1") (pinfunction "~{RESET}_1") (pintype "input"))
    )
    (net (code "12") (name "/SCL") (class "Default")
      (node (ref "IC15") (pin "5") (pinfunction "SCL_5") (pintype "input"))
      (node (ref "IC9") (pin "3") (pinfunction "SCLK_3") (pintype "input"))
      (node (ref "J1") (pin "9") (pinfunction "9_9") (pintype "bidirectional"))
    )
    (net (code "13") (name "/SDA") (class "Default")
      (node (ref "IC15") (pin "4") (pinfunction "SDA_4") (pintype "input"))
      (node (ref "IC9") (pin "4") (pinfunction "SDA_4") (pintype "bidirectional"))
      (node (ref "J1") (pin "4") (pinfunction "4_4") (pintype "bidirectional"))
    )
    (net (code "14") (name "/SIGNAL_GND") (class "Default")
      (node (ref "J1") (pin "15") (pinfunction "15_15") (pintype "bidirectional"))
    )
    (net (code "15") (name "/USER_IO") (class "Default")
      (node (ref "J1") (pin "1") (pinfunction "1_1") (pintype "bidirectional"))
    )
    (net (code "16") (name "/U_RFL_PWR") (class "Default")
      (node (ref "J1") (pin "10") (pinfunction "10_10") (pintype "bidirectional"))
    )
    (net (code "17") (name "/U_TX_PWR") (class "Default")
      (node (ref "J1") (pin "5") (pinfunction "5_5") (pintype "bidirectional"))
    )
    (net (code "18") (name "/meas_I_N8V") (class "Default")
      (node (ref "C46") (pin "1") (pinfunction "1_1") (pintype "passive"))
      (node (ref "IC9") (pin "10") (pinfunction "CH2_10") (pintype "input"))
      (node (ref "R55") (pin "2") (pinfunction "2_2") (pintype "passive"))
    )
    (net (code "19") (name "/meas_I_P6V") (class "Default")
      (node (ref "C44") (pin "1") (pinfunction "1_1") (pintype "passive"))
      (node (ref "IC9") (pin "11") (pinfunction "CH1_11") (pintype "input"))
      (node (ref "R53") (pin "2") (pinfunction "2_2") (pintype "passive"))
    )
    (net (code "20") (name "/meas_I_P29V") (class "Default")
      (node (ref "C39") (pin "1") (pinfunction "1_1") (pintype "passive"))
      (node (ref "IC9") (pin "12") (pinfunction "CH0_12") (pintype "input"))
      (node (ref "R45") (pin "2") (pinfunction "2_2") (pintype "passive"))
    )
    (net (code "21") (name "/meas_P3V3MP") (class "Default")
      (node (ref "C49") (pin "1") (pinfunction "1_1") (pintype "passive"))
      (node (ref "IC9") (pin "9") (pinfunction "CH3_9") (pintype "input"))
      (node (ref "R58") (pin "2") (pinfunction "2_2") (pintype "passive"))
      (node (ref "R59") (pin "1") (pinfunction "1_1") (pintype "passive"))
    )
    (net (code "22") (name "GND") (class "Default")
      (node (ref "C19") (pin "1") (pinfunction "1_1") (pintype "passive"))
      (node (ref "C20") (pin "1") (pinfunction "1_1") (pintype "passive"))
      (node (ref "C32") (pin "1") (pinfunction "1_1") (pintype "passive"))
      (node (ref "C33") (pin "1") (pinfunction "1_1") (pintype "passive"))
      (node (ref "C34") (pin "1") (pinfunction "1_1") (pintype "passive"))
      (node (ref "C36") (pin "1") (pinfunction "1_1") (pintype "passive"))
      (node (ref "C37") (pin "1") (pinfunction "1_1") (pintype "passive"))
      (node (ref "C39") (pin "2") (pinfunction "2_2") (pintype "passive"))
      (node (ref "C42") (pin "1") (pinfunction "1_1") (pintype "passive"))
      (node (ref "C43") (pin "1") (pinfunction "1_1") (pintype "passive"))
      (node (ref "C44") (pin "2") (pinfunction "2_2") (pintype "passive"))
      (node (ref "C45") (pin "1") (pinfunction "1_1") (pintype "passive"))
      (node (ref "C46") (pin "2") (pinfunction "2_2") (pintype "passive"))
      (node (ref "C47") (pin "1") (pinfunction "1_1") (pintype "passive"))
      (node (ref "C48") (pin "1") (pinfunction "1_1") (pintype "passive"))
      (node (ref "C49") (pin "2") (pinfunction "2_2") (pintype "passive"))
      (node (ref "C50") (pin "2") (pinfunction "2_2") (pintype "passive"))
      (node (ref "C51") (pin "2") (pinfunction "2_2") (pintype "passive"))
      (node (ref "C60") (pin "1") (pinfunction "1_1") (pintype "passive"))
      (node (ref "IC13") (pin "1") (pinfunction "GND_1") (pintype "power_in"))
      (node (ref "IC14") (pin "2") (pinfunction "GND_2") (pintype "power_in"))
      (node (ref "IC15") (pin "2") (pinfunction "GND_2") (pintype "power_in"))
      (node (ref "IC3") (pin "3") (pinfunction "GND_3") (pintype "power_in"))
      (node (ref "IC3") (pin "6") (pinfunction "GND_6") (pintype "power_in"))
      (node (ref "IC6") (pin "2") (pinfunction "GND_2") (pintype "power_in"))
      (node (ref "IC7") (pin "2") (pinfunction "GND_2") (pintype "power_in"))
      (node (ref "IC8") (pin "2") (pinfunction "GND_2") (pintype "power_in"))
      (node (ref "IC9") (pin "17") (pinfunction "EP_17") (pintype "power_in"))
      (node (ref "IC9") (pin "6") (pinfunction "DGND_6") (pintype "power_in"))
      (node (ref "IC9") (pin "8") (pinfunction "AGND_8") (pintype "power_in"))
      (node (ref "J1") (pin "11") (pinfunction "11_11") (pintype "bidirectional"))
      (node (ref "J1") (pin "16") (pinfunction "16_16") (pintype "passive"))
      (node (ref "J1") (pin "17") (pinfunction "17_17") (pintype "passive"))
      (node (ref "J1") (pin "6") (pinfunction "6_6") (pintype "bidirectional"))
      (node (ref "LD1") (pin "1") (pinfunction "C_1") (pintype "passive"))
      (node (ref "LD12") (pin "2") (pinfunction "A_2") (pintype "passive"))
      (node (ref "LD2") (pin "1") (pinfunction "C_1") (pintype "passive"))
      (node (ref "R13") (pin "1") (pinfunction "1_1") (pintype "passive"))
      (node (ref "R50") (pin "2") (pinfunction "2_2") (pintype "passive"))
      (node (ref "R51") (pin "1") (pinfunction "1_1") (pintype "passive"))
      (node (ref "R52") (pin "1") (pinfunction "1_1") (pintype "passive"))
      (node (ref "R59") (pin "2") (pinfunction "2_2") (pintype "passive"))
      (node (ref "R85") (pin "1") (pinfunction "1_1") (pintype "passive"))
      (node (ref "R9") (pin "1") (pinfunction "1_1") (pintype "passive"))
      (node (ref "R90") (pin "1") (pinfunction "1_1") (pintype "passive"))
      (node (ref "T2") (pin "2") (pinfunction "S_2") (pintype "passive"))
      (node (ref "T3") (pin "2") (pinfunction "S_2") (pintype "passive"))
      (node (ref "T6") (pin "2") (pinfunction "S_2") (pintype "passive"))
      (node (ref "U1") (pin "3") (pinfunction "GROUND_3") (pintype "power_in"))
      (node (ref "U1") (pin "4") (pinfunction "DRIVER_SOURCE_4") (pintype "passive"))
    )
    (net (code "23") (name "N8V0") (class "Default")
      (node (ref "C42") (pin "2") (pinfunction "2_2") (pintype "passive"))
      (node (ref "IC13") (pin "2") (pinfunction "IN_2") (pintype "input"))
    )
    (net (code "24") (name "Net-(D2-A)") (class "Default")
      (node (ref "D2") (pin "2") (pinfunction "A_2") (pintype "passive"))
      (node (ref "IC14") (pin "3") (pinfunction "EN_3") (pintype "input"))
      (node (ref "R88") (pin "1") (pinfunction "1_1") (pintype "passive"))
    )
    (net (code "25") (name "Net-(IC3-ADJ)") (class "Default")
      (node (ref "IC3") (pin "5") (pinfunction "ADJ_5") (pintype "input"))
      (node (ref "R10") (pin "1") (pinfunction "1_1") (pintype "passive"))
      (node (ref "R13") (pin "2") (pinfunction "2_2") (pintype "passive"))
    )
    (net (code "26") (name "Net-(IC3-OUT)") (class "Default")
      (node (ref "IC3") (pin "4") (pinfunction "OUT_4") (pintype "power_in"))
      (node (ref "R10") (pin "2") (pinfunction "2_2") (pintype "passive"))
      (node (ref "R11") (pin "1") (pinfunction "1_1") (pintype "passive"))
      (node (ref "R39") (pin "2") (pinfunction "2_2") (pintype "passive"))
      (node (ref "R49") (pin "2") (pinfunction "2_2") (pintype "passive"))
    )
    (net (code "27") (name "Net-(IC6-OUT)") (class "Default")
      (node (ref "IC6") (pin "1") (pinfunction "OUT_1") (pintype "output"))
      (node (ref "R45") (pin "1") (pinfunction "1_1") (pintype "passive"))
    )
    (net (code "28") (name "Net-(IC6-VIN+)") (class "Default")
      (node (ref "C38") (pin "2") (pinfunction "2_2") (pintype "passive"))
      (node (ref "IC6") (pin "3") (pinfunction "VIN+_3") (pintype "input"))
      (node (ref "R44") (pin "1") (pinfunction "1_1") (pintype "passive"))
    )
    (net (code "29") (name "Net-(IC6-VIN-)") (class "Default")
      (node (ref "C38") (pin "1") (pinfunction "1_1") (pintype "passive"))
      (node (ref "IC6") (pin "4") (pinfunction "VIN-_4") (pintype "input"))
      (node (ref "R43") (pin "1") (pinfunction "1_1") (pintype "passive"))
    )
    (net (code "30") (name "Net-(IC7-OUT)") (class "Default")
      (node (ref "IC7") (pin "1") (pinfunction "OUT_1") (pintype "output"))
      (node (ref "R53") (pin "1") (pinfunction "1_1") (pintype "passive"))
    )
    (net (code "31") (name "Net-(IC7-VIN+)") (class "Default")
      (node (ref "C41") (pin "2") (pinfunction "2_2") (pintype "passive"))
      (node (ref "IC7") (pin "3") (pinfunction "VIN+_3") (pintype "input"))
      (node (ref "R49") (pin "1") (pinfunction "1_1") (pintype "passive"))
    )
    (net (code "32") (name "Net-(IC7-VIN-)") (class "Default")
      (node (ref "C41") (pin "1") (pinfunction "1_1") (pintype "passive"))
      (node (ref "IC7") (pin "4") (pinfunction "VIN-_4") (pintype "input"))
      (node (ref "R48") (pin "1") (pinfunction "1_1") (pintype "passive"))
    )
    (net (code "33") (name "Net-(IC8-OUT)") (class "Default")
      (node (ref "IC8") (pin "1") (pinfunction "OUT_1") (pintype "output"))
      (node (ref "R55") (pin "1") (pinfunction "1_1") (pintype "passive"))
    )
    (net (code "34") (name "Net-(IC8-VIN+)") (class "Default")
      (node (ref "C40") (pin "1") (pinfunction "1_1") (pintype "passive"))
      (node (ref "IC8") (pin "3") (pinfunction "VIN+_3") (pintype "input"))
      (node (ref "R46") (pin "1") (pinfunction "1_1") (pintype "passive"))
    )
    (net (code "35") (name "Net-(IC8-VIN-)") (class "Default")
      (node (ref "C40") (pin "2") (pinfunction "2_2") (pintype "passive"))
      (node (ref "IC8") (pin "4") (pinfunction "VIN-_4") (pintype "input"))
      (node (ref "R47") (pin "1") (pinfunction "1_1") (pintype "passive"))
    )
    (net (code "36") (name "Net-(IC9-ADCIN)") (class "Default")
      (node (ref "C48") (pin "2") (pinfunction "2_2") (pintype "passive"))
      (node (ref "IC9") (pin "14") (pinfunction "ADCIN_14") (pintype "input"))
      (node (ref "R56") (pin "2") (pinfunction "2_2") (pintype "passive"))
    )
    (net (code "37") (name "Net-(IC9-MUXOUT)") (class "Default")
      (node (ref "IC9") (pin "13") (pinfunction "MUXOUT_13") (pintype "output"))
      (node (ref "R56") (pin "1") (pinfunction "1_1") (pintype "passive"))
    )
    (net (code "38") (name "Net-(IC13-ADJ)") (class "Default")
      (node (ref "IC13") (pin "4") (pinfunction "ADJ_4") (pintype "input"))
      (node (ref "R86") (pin "1") (pinfunction "1_1") (pintype "passive"))
      (node (ref "R87") (pin "2") (pinfunction "2_2") (pintype "passive"))
    )
    (net (code "39") (name "Net-(IC13-OUT)") (class "Default")
      (node (ref "IC13") (pin "5") (pinfunction "OUT_5") (pintype "power_in"))
      (node (ref "R104") (pin "1") (pinfunction "1_1") (pintype "passive"))
      (node (ref "R38") (pin "1") (pinfunction "1_1") (pintype "passive"))
      (node (ref "R46") (pin "2") (pinfunction "2_2") (pintype "passive"))
      (node (ref "R86") (pin "2") (pinfunction "2_2") (pintype "passive"))
    )
    (net (code "40") (name "Net-(IC13-~{SHDN})") (class "Default")
      (node (ref "IC13") (pin "3") (pinfunction "~{SHDN}_3") (pintype "input"))
      (node (ref "R54") (pin "2") (pinfunction "2_2") (pintype "passive"))
    )
    (net (code "41") (name "Net-(IC14-FLAG1)") (class "Default")
      (node (ref "IC14") (pin "6") (pinfunction "FLAG1_6") (pintype "output"))
      (node (ref "R54") (pin "1") (pinfunction "1_1") (pintype "passive"))
    )
    (net (code "42") (name "Net-(IC14-FLAG2)") (class "Default")
      (node (ref "IC14") (pin "5") (pinfunction "FLAG2_5") (pintype "output"))
      (node (ref "IC3") (pin "1") (pinfunction "~{SHDN}_1") (pintype "input"))
      (node (ref "R51") (pin "2") (pinfunction "2_2") (pintype "passive"))
    )
    (net (code "43") (name "Net-(IC14-FLAG3)") (class "Default")
      (node (ref "IC14") (pin "4") (pinfunction "FLAG3_4") (pintype "output"))
      (node (ref "R52") (pin "2") (pinfunction "2_2") (pintype "passive"))
      (node (ref "T6") (pin "1") (pinfunction "G_1") (pintype "passive"))
    )
    (net (code "44") (name "Net-(IC15-A0)") (class "Default")
      (node (ref "IC15") (pin "6") (pinfunction "A0_6") (pintype "input"))
      (node (ref "R90") (pin "2") (pinfunction "2_2") (pintype "passive"))
    )
    (net (code "45") (name "Net-(IC15-VOUT)") (class "Default")
      (node (ref "IC15") (pin "1") (pinfunction "VOUT_1") (pintype "output"))
      (node (ref "R87") (pin "1") (pinfunction "1_1") (pintype "passive"))
      (node (ref "R89") (pin "1") (pinfunction "1_1") (pintype "passive"))
    )
    (net (code "46") (name "Net-(LD1-A)") (class "Default")
      (node (ref "LD1") (pin "2") (pinfunction "A_2") (pintype "passive"))
      (node (ref "R7") (pin "1") (pinfunction "1_1") (pintype "passive"))
    )
    (net (code "47") (name "Net-(LD2-A)") (class "Default")
      (node (ref "LD2") (pin "2") (pinfunction "A_2") (pintype "passive"))
      (node (ref "R11") (pin "2") (pinfunction "2_2") (pintype "passive"))
    )
    (net (code "48") (name "Net-(LD4-A)") (class "Default")
      (node (ref "LD4") (pin "2") (pinfunction "A_2") (pintype "passive"))
      (node (ref "R107") (pin "1") (pinfunction "1_1") (pintype "passive"))
    )
    (net (code "49") (name "Net-(LD12-C)") (class "Default")
      (node (ref "LD12") (pin "1") (pinfunction "C_1") (pintype "passive"))
      (node (ref "R104") (pin "2") (pinfunction "2_2") (pintype "passive"))
    )
    (net (code "50") (name "Net-(T1-B)") (class "Default")
      (node (ref "R12") (pin "1") (pinfunction "1_1") (pintype "passive"))
      (node (ref "R29") (pin "2") (pinfunction "2_2") (pintype "passive"))
      (node (ref "T1") (pin "1") (pinfunction "B_1") (pintype "passive"))
    )
    (net (code "51") (name "Net-(T1-C)") (class "Default")
      (node (ref "R37") (pin "2") (pinfunction "2_2") (pintype "passive"))
      (node (ref "R44") (pin "2") (pinfunction "2_2") (pintype "passive"))
      (node (ref "R7") (pin "2") (pinfunction "2_2") (pintype "passive"))
      (node (ref "R8") (pin "2") (pinfunction "2_2") (pintype "passive"))
      (node (ref "T1") (pin "3") (pinfunction "C_3") (pintype "passive"))
    )
    (net (code "52") (name "Net-(T1-E)") (class "Default")
      (node (ref "R12") (pin "2") (pinfunction "2_2") (pintype "passive"))
      (node (ref "T1") (pin "2") (pinfunction "E_2") (pintype "passive"))
      (node (ref "U1") (pin "8") (pinfunction "SENSE_RESISTOR_OUT_8") (pintype "passive"))
    )
    (net (code "53") (name "Net-(T2-D)") (class "Default")
      (node (ref "J1") (pin "14") (pinfunction "14_14") (pintype "bidirectional"))
      (node (ref "R84") (pin "1") (pinfunction "1_1") (pintype "passive"))
      (node (ref "T2") (pin "3") (pinfunction "D_3") (pintype "passive"))
    )
    (net (code "54") (name "Net-(T2-G)") (class "Default")
      (node (ref "R40") (pin "1") (pinfunction "1_1") (pintype "passive"))
      (node (ref "T2") (pin "1") (pinfunction "G_1") (pintype "passive"))
      (node (ref "T3") (pin "1") (pinfunction "G_1") (pintype "passive"))
      (node (ref "T6") (pin "3") (pinfunction "D_3") (pintype "passive"))
    )
    (net (code "55") (name "Net-(T3-D)") (class "Default")
      (node (ref "C20") (pin "2") (pinfunction "2_2") (pintype "passive"))
      (node (ref "T3") (pin "3") (pinfunction "D_3") (pintype "passive"))
      (node (ref "U1") (pin "2") (pinfunction "COMPENSATION/SHUTDOWN_2") (pintype "passive"))
    )
    (net (code "56") (name "Net-(U1-DRIVER_SINK)") (class "Default")
      (node (ref "R29") (pin "1") (pinfunction "1_1") (pintype "passive"))
      (node (ref "U1") (pin "6") (pinfunction "DRIVER_SINK_6") (pintype "passive"))
    )
    (net (code "57") (name "Net-(U1-VOUT_SENSE)") (class "Default")
      (node (ref "R8") (pin "1") (pinfunction "1_1") (pintype "passive"))
      (node (ref "R9") (pin "2") (pinfunction "2_2") (pintype "passive"))
      (node (ref "U1") (pin "5") (pinfunction "VOUT_SENSE_5") (pintype "input"))
    )
    (net (code "58") (name "P3V3") (class "Default")
      (node (ref "C43") (pin "2") (pinfunction "2_2") (pintype "passive"))
      (node (ref "C45") (pin "2") (pinfunction "2_2") (pintype "passive"))
      (node (ref "C47") (pin "2") (pinfunction "2_2") (pintype "passive"))
      (node (ref "C50") (pin "1") (pinfunction "1_1") (pintype "passive"))
      (node (ref "C60") (pin "2") (pinfunction "2_2") (pintype "passive"))
      (node (ref "IC14") (pin "1") (pinfunction "VCC_1") (pintype "power_in"))
      (node (ref "IC15") (pin "3") (pinfunction "VDD_3") (pintype "power_in"))
      (node (ref "IC6") (pin "5") (pinfunction "V+_5") (pintype "power_in"))
      (node (ref "IC7") (pin "5") (pinfunction "V+_5") (pintype "power_in"))
      (node (ref "IC8") (pin "5") (pinfunction "V+_5") (pintype "power_in"))
      (node (ref "IC9") (pin "16") (pinfunction "DVDD_16") (pintype "power_in"))
      (node (ref "IC9") (pin "5") (pinfunction "A0_5") (pintype "input"))
      (node (ref "R107") (pin "2") (pinfunction "2_2") (pintype "passive"))
      (node (ref "R40") (pin "2") (pinfunction "2_2") (pintype "passive"))
      (node (ref "R57") (pin "2") (pinfunction "2_2") (pintype "passive"))
      (node (ref "R89") (pin "2") (pinfunction "2_2") (pintype "passive"))
    )
    (net (code "59") (name "P5V0") (class "Default")
      (node (ref "F1") (pin "1") (pinfunction "1_1") (pintype "passive"))
    )
    (net (code "60") (name "P6V5") (class "Default")
      (node (ref "C19") (pin "2") (pinfunction "2_2") (pintype "passive"))
      (node (ref "IC3") (pin "2") (pinfunction "IN_2") (pintype "input"))
    )
    (net (code "61") (name "P30V0") (class "Default")
      (node (ref "C32") (pin "2") (pinfunction "2_2") (pintype "passive"))
      (node (ref "U1") (pin "1") (pinfunction "+VIN_1") (pintype "power_in"))
    )
    (net (code "62") (name "unconnected-(IC9-PWRCON-Pad7)") (class "Default")
      (node (ref "IC9") (pin "7") (pinfunction "PWRCON_7") (pintype "output"))
    )
    (net (code "63") (name "unconnected-(U1-CURRENT_LIMIT(-)-Pad7)") (class "Default")
      (node (ref "U1") (pin "7") (pinfunction "CURRENT_LIMIT(-)_7") (pintype "input"))
    )
  )
)
